# ui-jetson-nano.net
KiCad netlist of a schematic drawn in Altium Designer
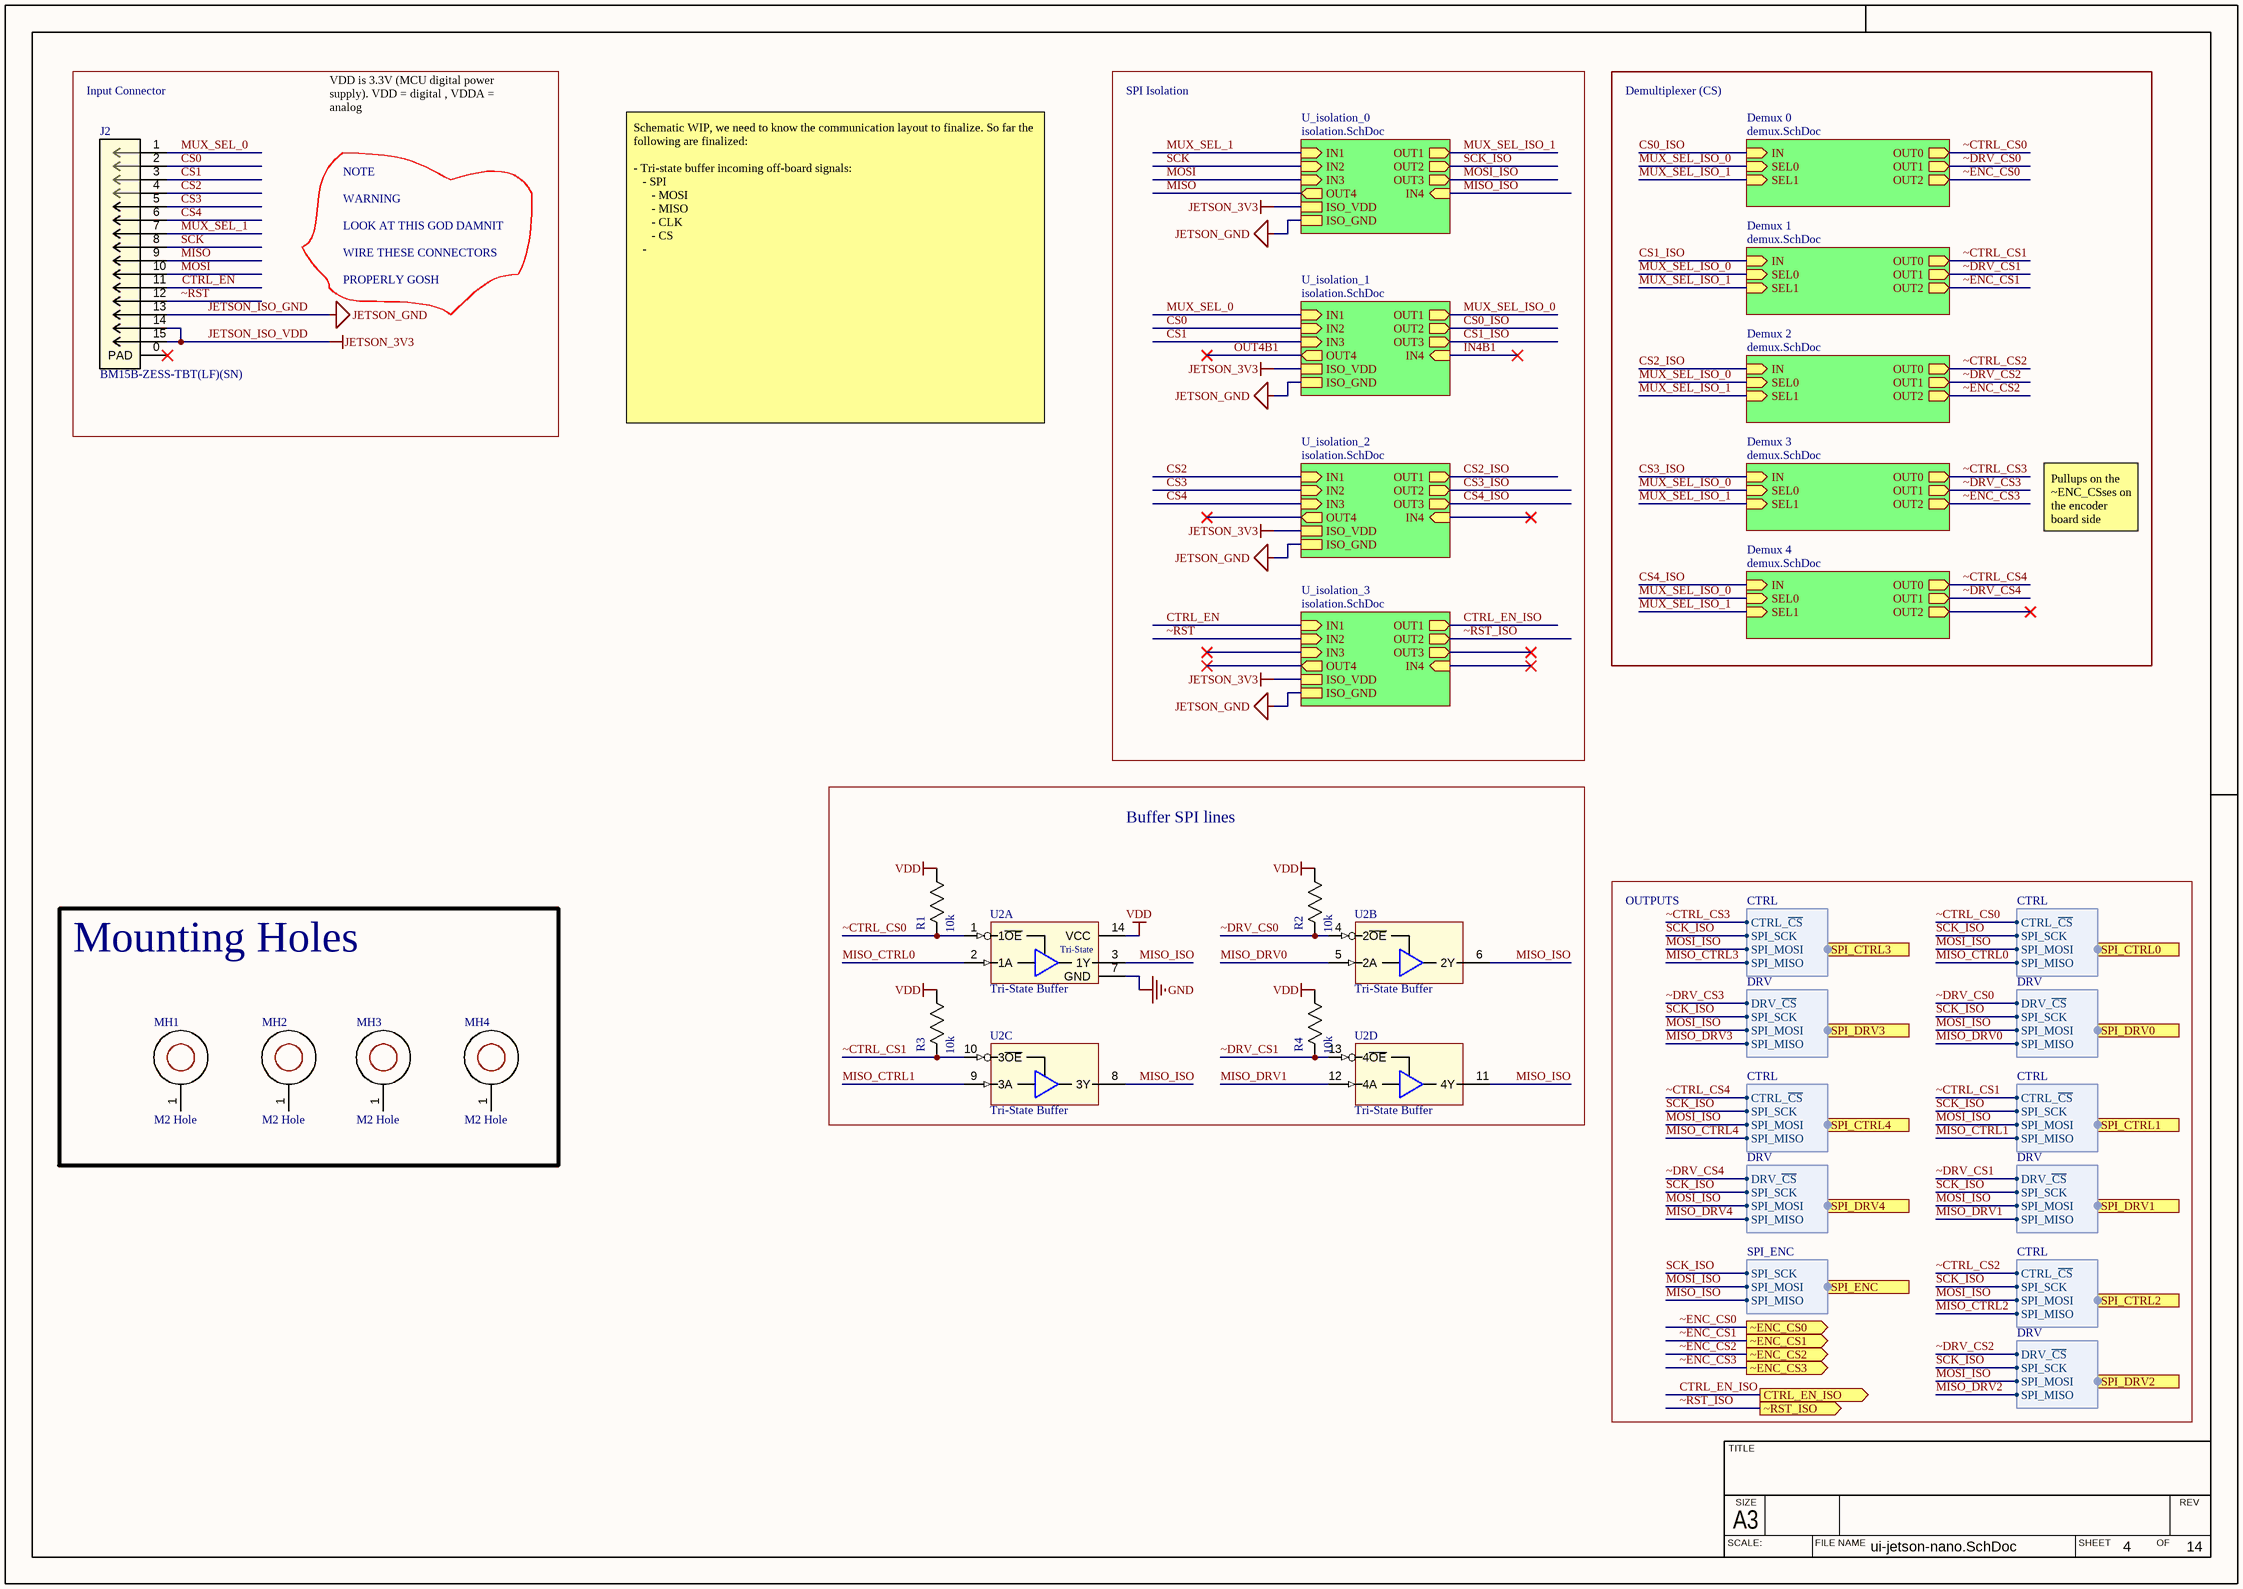
[diagram p0: ui-jetson-nano.SchDoc]

(export (version "E")
  (design (tool "Eeschema 10.0.6"))
  (components
    (comp (ref "J2")
      (value "BM15B-ZESS-TBT(LF)(SN)")
      (footprint "JST ZE SMT 15POS")
      (description "CONN HEADER VERT SMD 15POS ZE")
      (fields (field (name "PART NUMBER") "CN 15POS JST ZE SMT"))
      (libsource (lib "Connector_Library") (part "CN 15POS JST ZE SMT"))
    )
    (comp (ref "MH1")
      (value "M2 Hole")
      (footprint "Mounting Hole M2")
      (description "Standard M2 Mounting Hole for M2 Standoff")
      (fields (field (name "PART NUMBER") "MOUNTING HOLE M2"))
      (libsource (lib "IC_Library") (part "MOUNTING HOLE M2"))
    )
    (comp (ref "MH2")
      (value "M2 Hole")
      (footprint "Mounting Hole M2")
      (description "Standard M2 Mounting Hole for M2 Standoff")
      (fields (field (name "PART NUMBER") "MOUNTING HOLE M2"))
      (libsource (lib "IC_Library") (part "MOUNTING HOLE M2"))
    )
    (comp (ref "MH3")
      (value "M2 Hole")
      (footprint "Mounting Hole M2")
      (description "Standard M2 Mounting Hole for M2 Standoff")
      (fields (field (name "PART NUMBER") "MOUNTING HOLE M2"))
      (libsource (lib "IC_Library") (part "MOUNTING HOLE M2"))
    )
    (comp (ref "MH4")
      (value "M2 Hole")
      (footprint "Mounting Hole M2")
      (description "Standard M2 Mounting Hole for M2 Standoff")
      (fields (field (name "PART NUMBER") "MOUNTING HOLE M2"))
      (libsource (lib "IC_Library") (part "MOUNTING HOLE M2"))
    )
    (comp (ref "R1")
      (value "10k")
      (footprint "0603")
      (description "RES SMD 10K OHM 1% 1/8W 0805")
      (fields (field (name "TOLERANCE") "5%") (field (name "PART NUMBER") "RES 10k 1/8W 1%"))
      (libsource (lib "Resistor_Library") (part "RES_DEFAULT"))
    )
    (comp (ref "R2")
      (value "10k")
      (footprint "0603")
      (description "RES SMD 10K OHM 1% 1/8W 0805")
      (fields (field (name "TOLERANCE") "5%") (field (name "PART NUMBER") "RES 10k 1/8W 1%"))
      (libsource (lib "Resistor_Library") (part "RES_DEFAULT"))
    )
    (comp (ref "R3")
      (value "10k")
      (footprint "0603")
      (description "RES SMD 10K OHM 1% 1/8W 0805")
      (fields (field (name "TOLERANCE") "5%") (field (name "PART NUMBER") "RES 10k 1/8W 1%"))
      (libsource (lib "Resistor_Library") (part "RES_DEFAULT"))
    )
    (comp (ref "R4")
      (value "10k")
      (footprint "0603")
      (description "RES SMD 10K OHM 1% 1/8W 0805")
      (fields (field (name "TOLERANCE") "5%") (field (name "PART NUMBER") "RES 10k 1/8W 1%"))
      (libsource (lib "Resistor_Library") (part "RES_DEFAULT"))
    )
    (comp (ref "U2")
      (value "Tri-State Buffer")
      (footprint "14-TSSOP")
      (description "Buffer, Non-Inverting 4 Element 1 Bit per Element 3-State Output 14-TSSOP")
      (fields (field (name "PART NUMBER") "SN74LVC125APWR"))
      (libsource (lib "IC_Library") (part "SN74LVC125APWR"))
    )
  )
  (nets
    (net (code "4") (name "/CS0") (class "Default")
      (node (ref "J2") (pin "2") (pinfunction "2_2") (pintype "passive"))
    )
    (net (code "6") (name "/CS1") (class "Default")
      (node (ref "J2") (pin "3") (pinfunction "3_3") (pintype "passive"))
    )
    (net (code "8") (name "/CS2") (class "Default")
      (node (ref "J2") (pin "4") (pinfunction "4_4") (pintype "passive"))
    )
    (net (code "10") (name "/CS3") (class "Default")
      (node (ref "J2") (pin "5") (pinfunction "5_5") (pintype "passive"))
    )
    (net (code "12") (name "/CS4") (class "Default")
      (node (ref "J2") (pin "6") (pinfunction "6_6") (pintype "passive"))
    )
    (net (code "14") (name "/CTRL_EN") (class "Default")
      (node (ref "J2") (pin "11") (pinfunction "11_11") (pintype "passive"))
    )
    (net (code "20") (name "/MISO") (class "Default")
      (node (ref "J2") (pin "9") (pinfunction "9_9") (pintype "passive"))
    )
    (net (code "21") (name "/MISO_CTRL0") (class "Default")
      (node (ref "U2") (pin "2") (pinfunction "1A_2") (pintype "input"))
    )
    (net (code "22") (name "/MISO_CTRL1") (class "Default")
      (node (ref "U2") (pin "9") (pinfunction "3A_9") (pintype "input"))
    )
    (net (code "26") (name "/MISO_DRV0") (class "Default")
      (node (ref "U2") (pin "5") (pinfunction "2A_5") (pintype "input"))
    )
    (net (code "27") (name "/MISO_DRV1") (class "Default")
      (node (ref "U2") (pin "12") (pinfunction "4A_12") (pintype "input"))
    )
    (net (code "31") (name "/MISO_ISO") (class "Default")
      (node (ref "U2") (pin "11") (pinfunction "4Y_11") (pintype "passive"))
      (node (ref "U2") (pin "3") (pinfunction "1Y_3") (pintype "passive"))
      (node (ref "U2") (pin "6") (pinfunction "2Y_6") (pintype "passive"))
      (node (ref "U2") (pin "8") (pinfunction "3Y_8") (pintype "passive"))
    )
    (net (code "32") (name "/MOSI") (class "Default")
      (node (ref "J2") (pin "10") (pinfunction "10_10") (pintype "passive"))
    )
    (net (code "34") (name "/MUX_SEL_0") (class "Default")
      (node (ref "J2") (pin "1") (pinfunction "1_1") (pintype "passive"))
    )
    (net (code "35") (name "/MUX_SEL_1") (class "Default")
      (node (ref "J2") (pin "7") (pinfunction "7_7") (pintype "passive"))
    )
    (net (code "43") (name "/SCK") (class "Default")
      (node (ref "J2") (pin "8") (pinfunction "8_8") (pintype "passive"))
    )
    (net (code "48") (name "/~CTRL_CS0") (class "Default")
      (node (ref "R1") (pin "2") (pinfunction "R2_2") (pintype "passive"))
      (node (ref "U2") (pin "1") (pinfunction "1~{OE}_1") (pintype "input"))
    )
    (net (code "49") (name "/~CTRL_CS1") (class "Default")
      (node (ref "R3") (pin "2") (pinfunction "R2_2") (pintype "passive"))
      (node (ref "U2") (pin "10") (pinfunction "3~{OE}_10") (pintype "input"))
    )
    (net (code "53") (name "/~DRV_CS0") (class "Default")
      (node (ref "R2") (pin "2") (pinfunction "R2_2") (pintype "passive"))
      (node (ref "U2") (pin "4") (pinfunction "2~{OE}_4") (pintype "input"))
    )
    (net (code "54") (name "/~DRV_CS1") (class "Default")
      (node (ref "R4") (pin "2") (pinfunction "R2_2") (pintype "passive"))
      (node (ref "U2") (pin "13") (pinfunction "4~{OE}_13") (pintype "input"))
    )
    (net (code "62") (name "/~RST") (class "Default")
      (node (ref "J2") (pin "12") (pinfunction "12_12") (pintype "passive"))
    )
    (net (code "64") (name "GND") (class "Default")
      (node (ref "U2") (pin "7") (pinfunction "GND_7") (pintype "passive"))
    )
    (net (code "65") (name "JETSON_3V3") (class "Default")
      (node (ref "J2") (pin "14") (pinfunction "14_14") (pintype "passive"))
      (node (ref "J2") (pin "15") (pinfunction "15_15") (pintype "passive"))
    )
    (net (code "66") (name "JETSON_GND") (class "Default")
      (node (ref "J2") (pin "13") (pinfunction "13_13") (pintype "passive"))
    )
    (net (code "67") (name "VDD") (class "Default")
      (node (ref "R1") (pin "1") (pinfunction "R1_1") (pintype "passive"))
      (node (ref "R2") (pin "1") (pinfunction "R1_1") (pintype "passive"))
      (node (ref "R3") (pin "1") (pinfunction "R1_1") (pintype "passive"))
      (node (ref "R4") (pin "1") (pinfunction "R1_1") (pintype "passive"))
      (node (ref "U2") (pin "14") (pinfunction "VCC_14") (pintype "passive"))
    )
    (net (code "68") (name "unconnected-(J2-PAD-Pad0)") (class "Default")
      (node (ref "J2") (pin "0") (pinfunction "PAD_0") (pintype "passive+no_connect"))
    )
    (net (code "69") (name "unconnected-(MH1-Pad1)") (class "Default")
      (node (ref "MH1") (pin "1") (pinfunction "1_1") (pintype "passive"))
    )
    (net (code "70") (name "unconnected-(MH2-Pad1)") (class "Default")
      (node (ref "MH2") (pin "1") (pinfunction "1_1") (pintype "passive"))
    )
    (net (code "71") (name "unconnected-(MH3-Pad1)") (class "Default")
      (node (ref "MH3") (pin "1") (pinfunction "1_1") (pintype "passive"))
    )
    (net (code "72") (name "unconnected-(MH4-Pad1)") (class "Default")
      (node (ref "MH4") (pin "1") (pinfunction "1_1") (pintype "passive"))
    )
  )
)
